# ANALOG_INPUT.net
KiCad netlist of a schematic drawn in Altium Designer
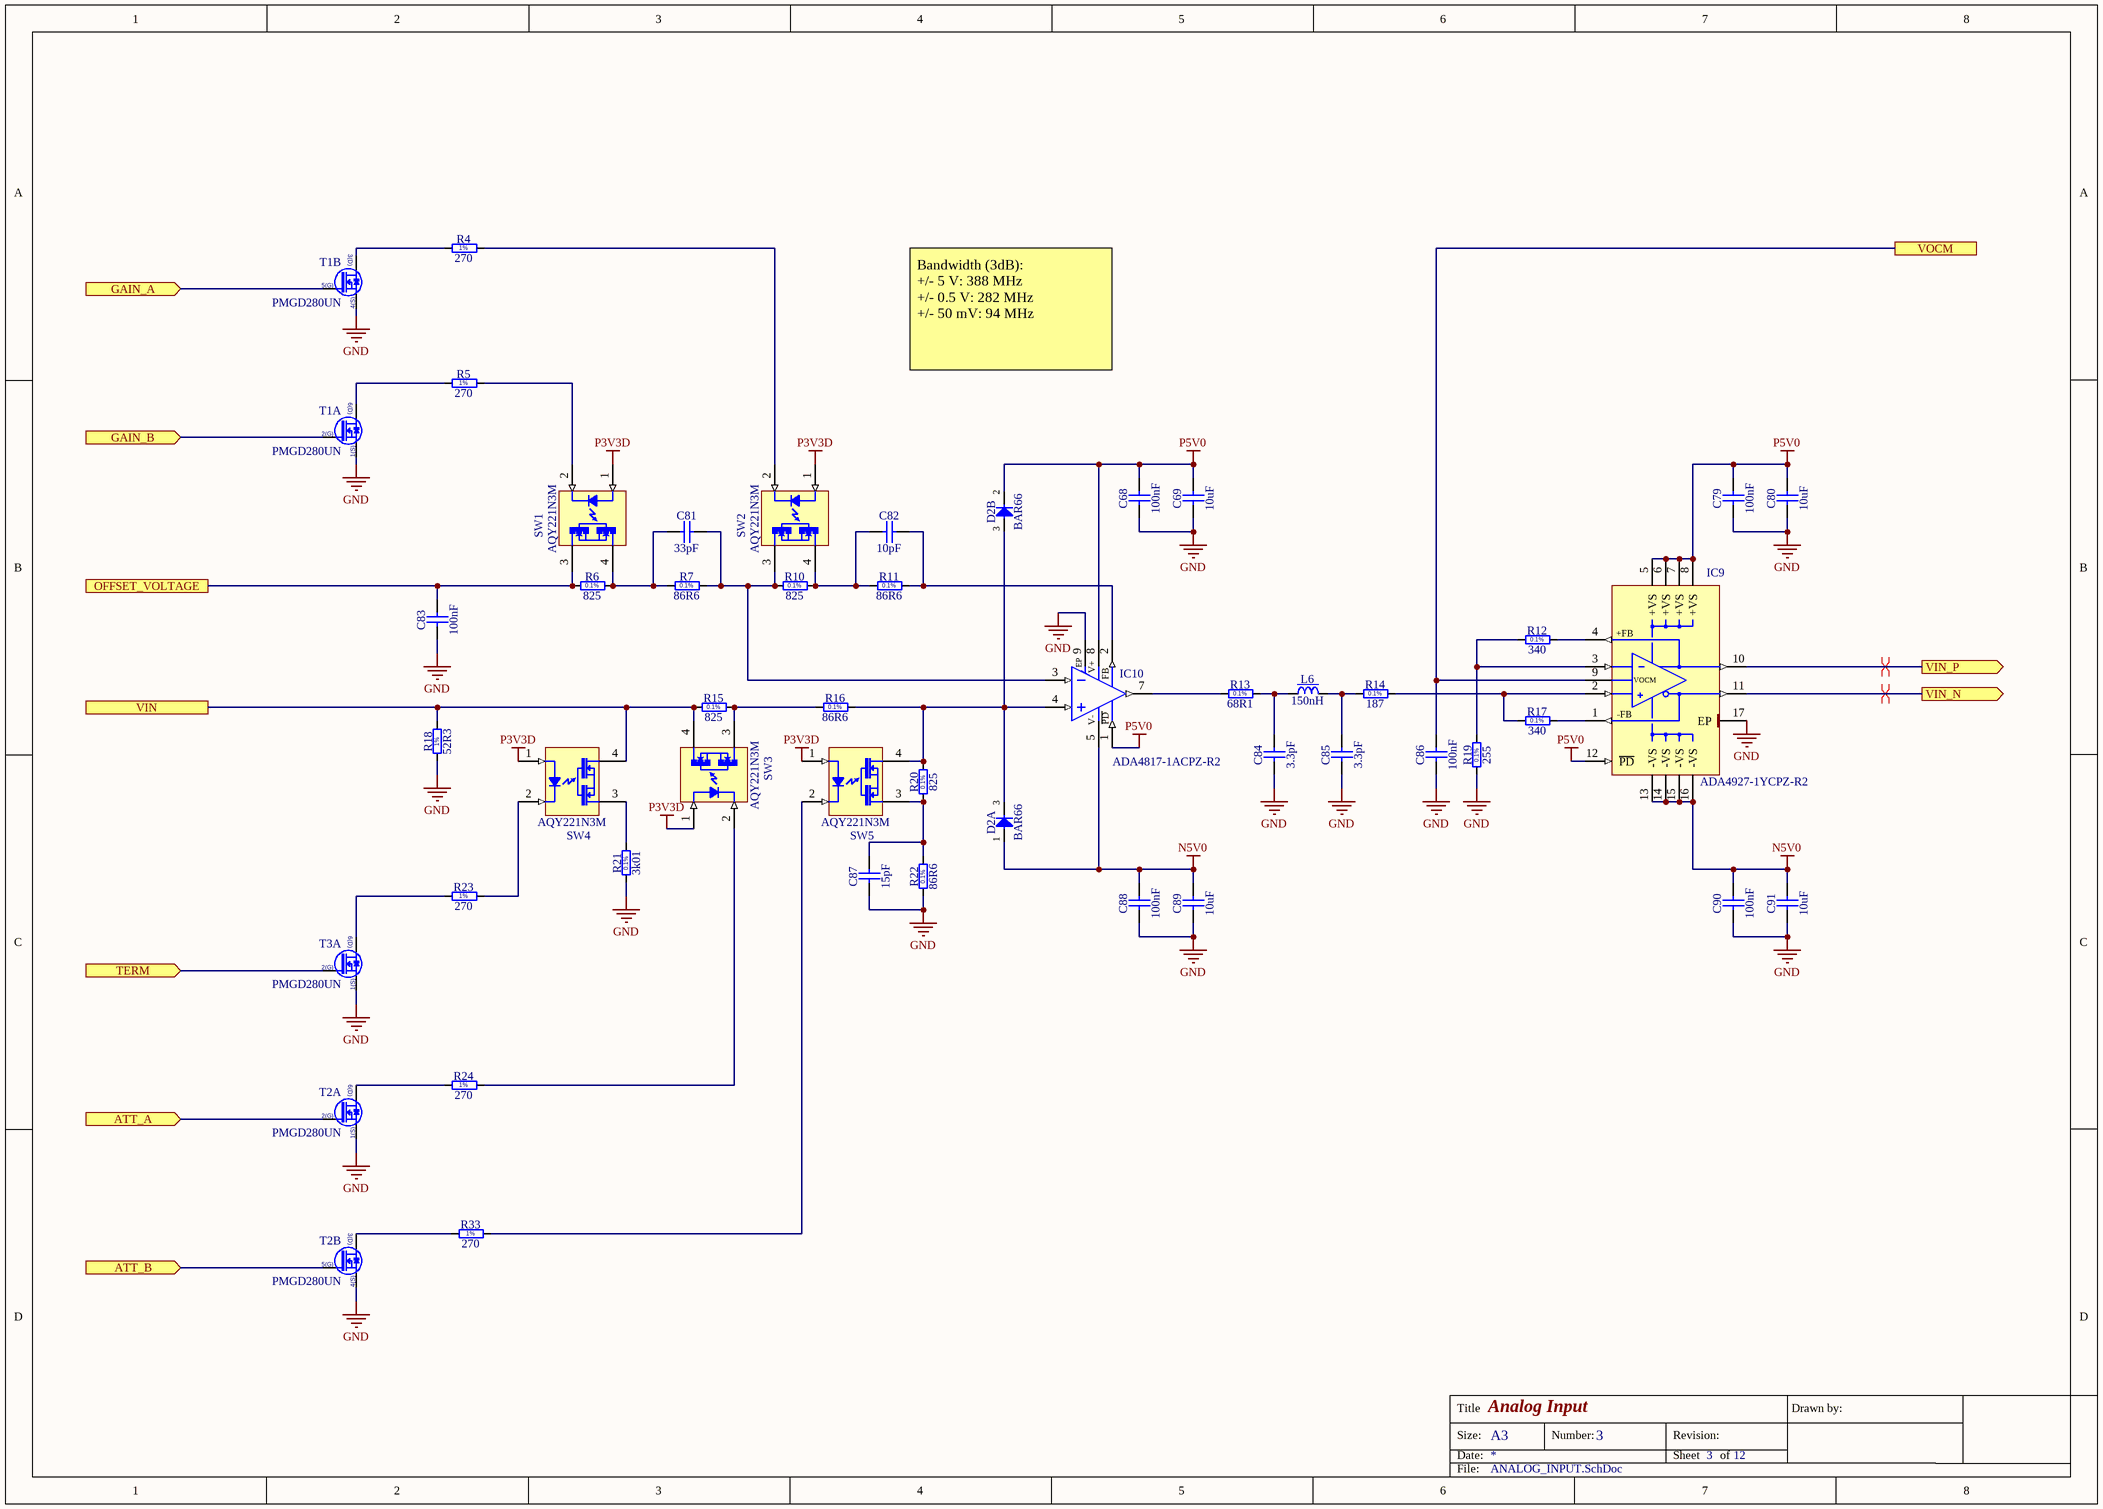
[diagram p0: ANALOG_INPUT.SchDoc]

(export (version "E")
  (design (tool "Eeschema 10.0.6"))
  (components
    (comp (ref "C68")
      (value "100nF")
      (footprint "CAPC1005X55N")
      (description "Non-polarised capacitor")
      (fields
        (field (name "PART NUMBER") "CC0402_100NF_16V_10%_X7R")
        (field (name "VOLTAGE") "16V")
        (field (name "AUTHOR") "CERN DEM JLC")
      )
      (libsource (lib "Capacitors") (part "Capacitor - non polarized"))
    )
    (comp (ref "C69")
      (value "10uF")
      (footprint "CAPC1608X80N")
      (description "Non-polarised capacitor")
      (fields
        (field (name "PART NUMBER") "CC0603_10UF_16V_20%_X5R")
        (field (name "VOLTAGE") "16V")
        (field (name "AUTHOR") "CERN DEM MR")
      )
      (libsource (lib "Capacitors") (part "Capacitor - non polarized"))
    )
    (comp (ref "C79")
      (value "100nF")
      (footprint "CAPC1005X55N")
      (description "Non-polarised capacitor")
      (fields
        (field (name "PART NUMBER") "CC0402_100NF_16V_10%_X7R")
        (field (name "VOLTAGE") "16V")
        (field (name "AUTHOR") "CERN DEM JLC")
      )
      (libsource (lib "Capacitors") (part "Capacitor - non polarized"))
    )
    (comp (ref "C80")
      (value "10uF")
      (footprint "CAPC1608X80N")
      (description "Non-polarised capacitor")
      (fields
        (field (name "PART NUMBER") "CC0603_10UF_16V_20%_X5R")
        (field (name "VOLTAGE") "16V")
        (field (name "AUTHOR") "CERN DEM MR")
      )
      (libsource (lib "Capacitors") (part "Capacitor - non polarized"))
    )
    (comp (ref "C81")
      (value "33pF")
      (footprint "CAPC1608X87N")
      (description "Non-polarised capacitor")
      (fields
        (field (name "PART NUMBER") "CC0603_33PF_50V_5%_NP0")
        (field (name "VOLTAGE") "50V")
        (field (name "AUTHOR") "CERN DEM JLC")
      )
      (libsource (lib "Capacitors") (part "Capacitor - non polarized"))
    )
    (comp (ref "C82")
      (value "10pF")
      (footprint "CAPC1608X87N")
      (description "Non-polarised capacitor")
      (fields
        (field (name "PART NUMBER") "CC0603_10PF_50V_5%_NP0")
        (field (name "VOLTAGE") "50V")
        (field (name "AUTHOR") "CERN DEM JLC")
      )
      (libsource (lib "Capacitors") (part "Capacitor - non polarized"))
    )
    (comp (ref "C83")
      (value "100nF")
      (footprint "CAPC1005X55N")
      (description "Non-polarised capacitor")
      (fields
        (field (name "PART NUMBER") "CC0402_100NF_16V_10%_X7R")
        (field (name "VOLTAGE") "16V")
        (field (name "AUTHOR") "CERN DEM JLC")
      )
      (libsource (lib "Capacitors") (part "Capacitor - non polarized"))
    )
    (comp (ref "C84")
      (value "3.3pF")
      (footprint "CAPC1005X55N")
      (description "Non-polarised capacitor")
      (fields
        (field (name "PART NUMBER") "CC0402_3.3PF_50V_0.25PF_C0G")
        (field (name "VOLTAGE") "50V")
        (field (name "AUTHOR") "CERN DEM JLC")
      )
      (libsource (lib "Capacitors") (part "Capacitor - non polarized"))
    )
    (comp (ref "C85")
      (value "3.3pF")
      (footprint "CAPC1005X55N")
      (description "Non-polarised capacitor")
      (fields
        (field (name "PART NUMBER") "CC0402_3.3PF_50V_0.25PF_C0G")
        (field (name "VOLTAGE") "50V")
        (field (name "AUTHOR") "CERN DEM JLC")
      )
      (libsource (lib "Capacitors") (part "Capacitor - non polarized"))
    )
    (comp (ref "C86")
      (value "100nF")
      (footprint "CAPC1005X55N")
      (description "Non-polarised capacitor")
      (fields
        (field (name "PART NUMBER") "CC0402_100NF_16V_10%_X7R")
        (field (name "VOLTAGE") "16V")
        (field (name "AUTHOR") "CERN DEM JLC")
      )
      (libsource (lib "Capacitors") (part "Capacitor - non polarized"))
    )
    (comp (ref "C87")
      (value "15pF")
      (footprint "CAPC1005X55N")
      (description "Non-polarised capacitor")
      (fields
        (field (name "PART NUMBER") "CC0402_15PF_50V_5%_C0G")
        (field (name "VOLTAGE") "50V")
        (field (name "AUTHOR") "CERN DEM JLC")
      )
      (libsource (lib "Capacitors") (part "Capacitor - non polarized"))
    )
    (comp (ref "C88")
      (value "100nF")
      (footprint "CAPC1005X55N")
      (description "Non-polarised capacitor")
      (fields
        (field (name "PART NUMBER") "CC0402_100NF_16V_10%_X7R")
        (field (name "VOLTAGE") "16V")
        (field (name "AUTHOR") "CERN DEM JLC")
      )
      (libsource (lib "Capacitors") (part "Capacitor - non polarized"))
    )
    (comp (ref "C89")
      (value "10uF")
      (footprint "CAPC1608X80N")
      (description "Non-polarised capacitor")
      (fields
        (field (name "PART NUMBER") "CC0603_10UF_16V_20%_X5R")
        (field (name "VOLTAGE") "16V")
        (field (name "AUTHOR") "CERN DEM MR")
      )
      (libsource (lib "Capacitors") (part "Capacitor - non polarized"))
    )
    (comp (ref "C90")
      (value "100nF")
      (footprint "CAPC1005X55N")
      (description "Non-polarised capacitor")
      (fields
        (field (name "PART NUMBER") "CC0402_100NF_16V_10%_X7R")
        (field (name "VOLTAGE") "16V")
        (field (name "AUTHOR") "CERN DEM JLC")
      )
      (libsource (lib "Capacitors") (part "Capacitor - non polarized"))
    )
    (comp (ref "C91")
      (value "10uF")
      (footprint "CAPC1608X80N")
      (description "Non-polarised capacitor")
      (fields
        (field (name "PART NUMBER") "CC0603_10UF_16V_20%_X5R")
        (field (name "VOLTAGE") "16V")
        (field (name "AUTHOR") "CERN DEM MR")
      )
      (libsource (lib "Capacitors") (part "Capacitor - non polarized"))
    )
    (comp (ref "D2")
      (value "BAR66")
      (footprint "SOT95P240X110-3N")
      (description "Serial Diode")
      (fields
        (field (name "VOLTAGE") "150V")
        (field (name "POWER") "250mA")
        (field (name "AUTHOR") "CERN DEM JLC")
      )
      (libsource (lib "ICs And Semiconductors") (part "Diode x2 A1C3_A3C2"))
    )
    (comp (ref "IC9")
      (value "ADA4927-1YCPZ-R2")
      (footprint "QFN50P300X300X100-17N-S145")
      (description "Ultralow Distortion Current Feedback Differential ADC Driver")
      (fields (field (name "MANUFACTURER") "ANALOG DEVICES") (field (name "AUTHOR") "CERN DEM JLC"))
      (libsource (lib "ICs And Semiconductors") (part "ADA4927-1"))
    )
    (comp (ref "IC10")
      (value "ADA4817-1ACPZ-R2")
      (footprint "SON50P300X300X90-9N-R160X189")
      (description "Low Noise, 1GHz FastFEET Operational Amplifier")
      (fields (field (name "MANUFACTURER") "ANALOG DEVICES") (field (name "AUTHOR") "CERN DEM JLC"))
      (libsource (lib "ICs And Semiconductors") (part "ADA4817-1ACPZ"))
    )
    (comp (ref "L6")
      (value "150nH")
      (footprint "IND_COILCRAFT_0805CS")
      (description "Inductor With Core")
      (fields
        (field (name "PART NUMBER") "IND_150NH_2%_COILCRAFT_0805CS")
        (field (name "POWER") "400mA")
        (field (name "AUTHOR") "CERN DEM JLC")
      )
      (libsource (lib "Inductors & Transformers") (part "Inductor With Magnetic core"))
    )
    (comp (ref "R4")
      (value "270")
      (footprint "RESC1608X55N")
      (description "Resistor - 1%")
      (fields
        (field (name "PART NUMBER") "R0603_270R_1%_0.1W_100PPM")
        (field (name "POWER") "0.1W")
        (field (name "AUTHOR") "CERN DEM JLC")
      )
      (libsource (lib "Resistors") (part "Resistor - 1%"))
    )
    (comp (ref "R5")
      (value "270")
      (footprint "RESC1608X55N")
      (description "Resistor - 1%")
      (fields
        (field (name "PART NUMBER") "R0603_270R_1%_0.1W_100PPM")
        (field (name "POWER") "0.1W")
        (field (name "AUTHOR") "CERN DEM JLC")
      )
      (libsource (lib "Resistors") (part "Resistor - 1%"))
    )
    (comp (ref "R6")
      (value "825")
      (footprint "RESC1608X55N")
      (description "Resistor - 0.1%")
      (fields
        (field (name "PART NUMBER") "R0603_825R_0.1%_0.063W_10PPM")
        (field (name "POWER") "0.063W")
        (field (name "AUTHOR") "CERN DEM JLC")
      )
      (libsource (lib "Resistors") (part "Resistor - 0.1%"))
    )
    (comp (ref "R7")
      (value "86R6")
      (footprint "RESC1608X55N")
      (description "Resistor - 0.1%")
      (fields
        (field (name "PART NUMBER") "R0603_86R6_0.1%_0.1W_15PPM")
        (field (name "POWER") "0.1W")
        (field (name "AUTHOR") "CERN DEM JLC")
      )
      (libsource (lib "Resistors") (part "Resistor - 0.1%"))
    )
    (comp (ref "R10")
      (value "825")
      (footprint "RESC1608X55N")
      (description "Resistor - 0.1%")
      (fields
        (field (name "PART NUMBER") "R0603_825R_0.1%_0.063W_10PPM")
        (field (name "POWER") "0.063W")
        (field (name "AUTHOR") "CERN DEM JLC")
      )
      (libsource (lib "Resistors") (part "Resistor - 0.1%"))
    )
    (comp (ref "R11")
      (value "86R6")
      (footprint "RESC1608X55N")
      (description "Resistor - 0.1%")
      (fields
        (field (name "PART NUMBER") "R0603_86R6_0.1%_0.1W_15PPM")
        (field (name "POWER") "0.1W")
        (field (name "AUTHOR") "CERN DEM JLC")
      )
      (libsource (lib "Resistors") (part "Resistor - 0.1%"))
    )
    (comp (ref "R12")
      (value "340")
      (footprint "RESC1608X55N")
      (description "Resistor - 0.1%")
      (fields
        (field (name "PART NUMBER") "R0603_340R_0.1%_0.063W_10PPM")
        (field (name "POWER") "0.063W")
        (field (name "AUTHOR") "CERN DEM JLC")
      )
      (libsource (lib "Resistors") (part "Resistor - 0.1%"))
    )
    (comp (ref "R13")
      (value "68R1")
      (footprint "RESC1608X55N")
      (description "Resistor - 0.1%")
      (fields
        (field (name "PART NUMBER") "R0603_68R1_0.1%_0.063W_10PPM")
        (field (name "POWER") "0.063W")
        (field (name "AUTHOR") "CERN DEM JLC")
      )
      (libsource (lib "Resistors") (part "Resistor - 0.1%"))
    )
    (comp (ref "R14")
      (value "187")
      (footprint "RESC1608X55N")
      (description "Resistor - 0.1%")
      (fields
        (field (name "PART NUMBER") "R0603_187R_0.1%_0.063W_10PPM")
        (field (name "POWER") "0.063W")
        (field (name "AUTHOR") "CERN DEM JLC")
      )
      (libsource (lib "Resistors") (part "Resistor - 0.1%"))
    )
    (comp (ref "R15")
      (value "825")
      (footprint "RESC1608X55N")
      (description "Resistor - 0.1%")
      (fields
        (field (name "PART NUMBER") "R0603_825R_0.1%_0.063W_10PPM")
        (field (name "POWER") "0.063W")
        (field (name "AUTHOR") "CERN DEM JLC")
      )
      (libsource (lib "Resistors") (part "Resistor - 0.1%"))
    )
    (comp (ref "R16")
      (value "86R6")
      (footprint "RESC1608X55N")
      (description "Resistor - 0.1%")
      (fields
        (field (name "PART NUMBER") "R0603_86R6_0.1%_0.1W_15PPM")
        (field (name "POWER") "0.1W")
        (field (name "AUTHOR") "CERN DEM JLC")
      )
      (libsource (lib "Resistors") (part "Resistor - 0.1%"))
    )
    (comp (ref "R17")
      (value "340")
      (footprint "RESC1608X55N")
      (description "Resistor - 0.1%")
      (fields
        (field (name "PART NUMBER") "R0603_340R_0.1%_0.063W_10PPM")
        (field (name "POWER") "0.063W")
        (field (name "AUTHOR") "CERN DEM JLC")
      )
      (libsource (lib "Resistors") (part "Resistor - 0.1%"))
    )
    (comp (ref "R18")
      (value "52R3")
      (footprint "RESC6331X70N")
      (description "Resistor - 1%")
      (fields
        (field (name "PART NUMBER") "R2512_52R3_1%_1W_100PPM")
        (field (name "POWER") "1W")
        (field (name "AUTHOR") "*")
      )
      (libsource (lib "FMC_ADC") (part "R2512_52R3_1%_1W_100PPM"))
    )
    (comp (ref "R19")
      (value "255")
      (footprint "RESC1608X55N")
      (description "Resistor - 0.1%")
      (fields
        (field (name "PART NUMBER") "R0603_255R_0.1%_0.063W_10PPM")
        (field (name "POWER") "0.063W")
        (field (name "AUTHOR") "CERN DEM JLC")
      )
      (libsource (lib "Resistors") (part "Resistor - 0.1%"))
    )
    (comp (ref "R20")
      (value "825")
      (footprint "RESC1608X55N")
      (description "Resistor - 0.1%")
      (fields
        (field (name "PART NUMBER") "R0603_825R_0.1%_0.063W_10PPM")
        (field (name "POWER") "0.063W")
        (field (name "AUTHOR") "CERN DEM JLC")
      )
      (libsource (lib "Resistors") (part "Resistor - 0.1%"))
    )
    (comp (ref "R21")
      (value "3k01")
      (footprint "RESC1608X55N")
      (description "Resistor - 0.1%")
      (fields
        (field (name "PART NUMBER") "R0603_3K01_0.1%_0.063W_10PPM")
        (field (name "POWER") "0.063W")
        (field (name "AUTHOR") "CERN DEM JLC")
      )
      (libsource (lib "Resistors") (part "Resistor - 0.1%"))
    )
    (comp (ref "R22")
      (value "86R6")
      (footprint "RESC1608X55N")
      (description "Resistor - 0.1%")
      (fields
        (field (name "PART NUMBER") "R0603_86R6_0.1%_0.1W_15PPM")
        (field (name "POWER") "0.1W")
        (field (name "AUTHOR") "CERN DEM JLC")
      )
      (libsource (lib "Resistors") (part "Resistor - 0.1%"))
    )
    (comp (ref "R23")
      (value "270")
      (footprint "RESC1608X55N")
      (description "Resistor - 1%")
      (fields
        (field (name "PART NUMBER") "R0603_270R_1%_0.1W_100PPM")
        (field (name "POWER") "0.1W")
        (field (name "AUTHOR") "CERN DEM JLC")
      )
      (libsource (lib "Resistors") (part "Resistor - 1%"))
    )
    (comp (ref "R24")
      (value "270")
      (footprint "RESC1608X55N")
      (description "Resistor - 1%")
      (fields
        (field (name "PART NUMBER") "R0603_270R_1%_0.1W_100PPM")
        (field (name "POWER") "0.1W")
        (field (name "AUTHOR") "CERN DEM JLC")
      )
      (libsource (lib "Resistors") (part "Resistor - 1%"))
    )
    (comp (ref "R33")
      (value "270")
      (footprint "RESC1608X55N")
      (description "Resistor - 1%")
      (fields
        (field (name "PART NUMBER") "R0603_270R_1%_0.1W_100PPM")
        (field (name "POWER") "0.1W")
        (field (name "AUTHOR") "CERN DEM JLC")
      )
      (libsource (lib "Resistors") (part "Resistor - 1%"))
    )
    (comp (ref "SW1")
      (value "AQY221N3M")
      (footprint "PANASONIC_AQY22(SON)")
      (description "PhotoMOS Relay")
      (fields (field (name "MANUFACTURER") "PANASONIC ELECTRIC WORKS") (field (name "AUTHOR") "CERN DEM JLC"))
      (libsource (lib "ICs And Semiconductors") (part "PhotoMOS Relay x1 Type2"))
    )
    (comp (ref "SW2")
      (value "AQY221N3M")
      (footprint "PANASONIC_AQY22(SON)")
      (description "PhotoMOS Relay")
      (fields (field (name "MANUFACTURER") "PANASONIC ELECTRIC WORKS") (field (name "AUTHOR") "CERN DEM JLC"))
      (libsource (lib "ICs And Semiconductors") (part "PhotoMOS Relay x1 Type2"))
    )
    (comp (ref "SW3")
      (value "AQY221N3M")
      (footprint "PANASONIC_AQY22(SON)")
      (description "PhotoMOS Relay")
      (fields (field (name "MANUFACTURER") "PANASONIC ELECTRIC WORKS") (field (name "AUTHOR") "CERN DEM JLC"))
      (libsource (lib "") (part "PhotoMOS Relay x1 Type2_2"))
    )
    (comp (ref "SW4")
      (value "AQY221N3M")
      (footprint "PANASONIC_AQY22(SON)")
      (description "PhotoMOS Relay")
      (fields (field (name "MANUFACTURER") "PANASONIC ELECTRIC WORKS") (field (name "AUTHOR") "CERN DEM JLC"))
      (libsource (lib "") (part "PhotoMOS Relay x1 Type2_1"))
    )
    (comp (ref "SW5")
      (value "AQY221N3M")
      (footprint "PANASONIC_AQY22(SON)")
      (description "PhotoMOS Relay")
      (fields (field (name "MANUFACTURER") "PANASONIC ELECTRIC WORKS") (field (name "AUTHOR") "CERN DEM JLC"))
      (libsource (lib "") (part "PhotoMOS Relay x1 Type2_1"))
    )
    (comp (ref "T1")
      (value "PMGD280UN")
      (footprint "SOT65P210X110-6N")
      (description "Dual N-Channel micro TrenchMOS™ Ultra Low Level FET")
      (fields (field (name "MANUFACTURER") "NXP SEMICONDUCTORS") (field (name "AUTHOR") "CERN DEM JLC"))
      (libsource (lib "ICs And Semiconductors") (part "PMGD280UN"))
    )
    (comp (ref "T2")
      (value "PMGD280UN")
      (footprint "SOT65P210X110-6N")
      (description "Dual N-Channel micro TrenchMOS™ Ultra Low Level FET")
      (fields (field (name "MANUFACTURER") "NXP SEMICONDUCTORS") (field (name "AUTHOR") "CERN DEM JLC"))
      (libsource (lib "ICs And Semiconductors") (part "PMGD280UN"))
    )
    (comp (ref "T3")
      (value "PMGD280UN")
      (footprint "SOT65P210X110-6N")
      (description "Dual N-Channel micro TrenchMOS™ Ultra Low Level FET")
      (fields (field (name "MANUFACTURER") "NXP SEMICONDUCTORS") (field (name "AUTHOR") "CERN DEM JLC"))
      (libsource (lib "ICs And Semiconductors") (part "PMGD280UN"))
    )
  )
  (nets
    (net (code "1") (name "/ATT_A") (class "Default")
      (node (ref "T2") (pin "2") (pinfunction "G_2") (pintype "passive"))
    )
    (net (code "2") (name "/ATT_B") (class "Default")
      (node (ref "T2") (pin "5") (pinfunction "G_5") (pintype "passive"))
    )
    (net (code "3") (name "/GAIN_A") (class "Default")
      (node (ref "T1") (pin "5") (pinfunction "G_5") (pintype "passive"))
    )
    (net (code "4") (name "/GAIN_B") (class "Default")
      (node (ref "T1") (pin "2") (pinfunction "G_2") (pintype "passive"))
    )
    (net (code "5") (name "/OFFSET_VOLTAGE") (class "Default")
      (node (ref "C83") (pin "2") (pinfunction "2_2") (pintype "passive"))
      (node (ref "R6") (pin "1") (pinfunction "1_1") (pintype "passive"))
      (node (ref "SW1") (pin "3") (pinfunction "C_3") (pintype "open_collector"))
    )
    (net (code "6") (name "/TERM") (class "Default")
      (node (ref "T3") (pin "2") (pinfunction "G_2") (pintype "passive"))
    )
    (net (code "7") (name "/VIN") (class "Default")
      (node (ref "R15") (pin "1") (pinfunction "1_1") (pintype "passive"))
      (node (ref "R18") (pin "2") (pinfunction "2_2") (pintype "passive"))
      (node (ref "SW3") (pin "4") (pinfunction "E_4") (pintype "open_emitter"))
      (node (ref "SW4") (pin "4") (pinfunction "E_4") (pintype "open_emitter"))
    )
    (net (code "8") (name "/VIN_N") (class "Default")
      (node (ref "IC9") (pin "11") (pinfunction "-OUT_11") (pintype "output"))
    )
    (net (code "9") (name "/VIN_P") (class "Default")
      (node (ref "IC9") (pin "10") (pinfunction "+OUT_10") (pintype "output"))
    )
    (net (code "10") (name "/VOCM") (class "Default")
      (node (ref "C86") (pin "2") (pinfunction "2_2") (pintype "passive"))
      (node (ref "IC9") (pin "9") (pinfunction "VOCM_9") (pintype "passive"))
    )
    (net (code "11") (name "GND") (class "Default")
      (node (ref "C68") (pin "1") (pinfunction "1_1") (pintype "passive"))
      (node (ref "C69") (pin "1") (pinfunction "1_1") (pintype "passive"))
      (node (ref "C79") (pin "1") (pinfunction "1_1") (pintype "passive"))
      (node (ref "C80") (pin "1") (pinfunction "1_1") (pintype "passive"))
      (node (ref "C83") (pin "1") (pinfunction "1_1") (pintype "passive"))
      (node (ref "C84") (pin "1") (pinfunction "1_1") (pintype "passive"))
      (node (ref "C85") (pin "1") (pinfunction "1_1") (pintype "passive"))
      (node (ref "C86") (pin "1") (pinfunction "1_1") (pintype "passive"))
      (node (ref "C87") (pin "1") (pinfunction "1_1") (pintype "passive"))
      (node (ref "C88") (pin "1") (pinfunction "1_1") (pintype "passive"))
      (node (ref "C89") (pin "1") (pinfunction "1_1") (pintype "passive"))
      (node (ref "C90") (pin "1") (pinfunction "1_1") (pintype "passive"))
      (node (ref "C91") (pin "1") (pinfunction "1_1") (pintype "passive"))
      (node (ref "IC10") (pin "9") (pinfunction "EP_9") (pintype "power_in"))
      (node (ref "IC9") (pin "17") (pinfunction "EP_17") (pintype "power_in"))
      (node (ref "R18") (pin "1") (pinfunction "1_1") (pintype "passive"))
      (node (ref "R19") (pin "1") (pinfunction "1_1") (pintype "passive"))
      (node (ref "R21") (pin "1") (pinfunction "1_1") (pintype "passive"))
      (node (ref "R22") (pin "1") (pinfunction "1_1") (pintype "passive"))
      (node (ref "T1") (pin "1") (pinfunction "S_1") (pintype "passive"))
      (node (ref "T1") (pin "4") (pinfunction "S_4") (pintype "passive"))
      (node (ref "T2") (pin "1") (pinfunction "S_1") (pintype "passive"))
      (node (ref "T2") (pin "4") (pinfunction "S_4") (pintype "passive"))
      (node (ref "T3") (pin "1") (pinfunction "S_1") (pintype "passive"))
    )
    (net (code "12") (name "N5V0") (class "Default")
      (node (ref "C88") (pin "2") (pinfunction "2_2") (pintype "passive"))
      (node (ref "C89") (pin "2") (pinfunction "2_2") (pintype "passive"))
      (node (ref "C90") (pin "2") (pinfunction "2_2") (pintype "passive"))
      (node (ref "C91") (pin "2") (pinfunction "2_2") (pintype "passive"))
      (node (ref "D2") (pin "1") (pinfunction "A_1") (pintype "passive"))
      (node (ref "IC10") (pin "5") (pinfunction "-Vs_5") (pintype "power_in"))
      (node (ref "IC9") (pin "13") (pinfunction "-VS_13") (pintype "power_in"))
      (node (ref "IC9") (pin "14") (pinfunction "-VS_14") (pintype "power_in"))
      (node (ref "IC9") (pin "15") (pinfunction "-VS_15") (pintype "power_in"))
      (node (ref "IC9") (pin "16") (pinfunction "-VS_16") (pintype "power_in"))
    )
    (net (code "13") (name "Net-(C84-Pad2)") (class "Default")
      (node (ref "C84") (pin "2") (pinfunction "2_2") (pintype "passive"))
      (node (ref "L6") (pin "1") (pinfunction "1_1") (pintype "passive"))
      (node (ref "R13") (pin "2") (pinfunction "2_2") (pintype "passive"))
    )
    (net (code "14") (name "Net-(C85-Pad2)") (class "Default")
      (node (ref "C85") (pin "2") (pinfunction "2_2") (pintype "passive"))
      (node (ref "L6") (pin "2") (pinfunction "2_2") (pintype "passive"))
      (node (ref "R14") (pin "1") (pinfunction "1_1") (pintype "passive"))
    )
    (net (code "15") (name "Net-(D2A-COMAC)") (class "Default")
      (node (ref "D2") (pin "3") (pinfunction "COMAC_3") (pintype "passive"))
      (node (ref "IC10") (pin "4") (pinfunction "IN+_4") (pintype "input"))
      (node (ref "R16") (pin "2") (pinfunction "2_2") (pintype "passive"))
      (node (ref "R20") (pin "2") (pinfunction "2_2") (pintype "passive"))
      (node (ref "SW5") (pin "4") (pinfunction "E_4") (pintype "open_emitter"))
    )
    (net (code "16") (name "Net-(IC9-+FB)") (class "Default")
      (node (ref "IC9") (pin "4") (pinfunction "+FB_4") (pintype "output"))
      (node (ref "R12") (pin "2") (pinfunction "2_2") (pintype "passive"))
    )
    (net (code "17") (name "Net-(IC9-+IN)") (class "Default")
      (node (ref "IC9") (pin "2") (pinfunction "+IN_2") (pintype "input"))
      (node (ref "R14") (pin "2") (pinfunction "2_2") (pintype "passive"))
      (node (ref "R17") (pin "1") (pinfunction "1_1") (pintype "passive"))
    )
    (net (code "18") (name "Net-(IC9--FB)") (class "Default")
      (node (ref "IC9") (pin "1") (pinfunction "-FB_1") (pintype "output"))
      (node (ref "R17") (pin "2") (pinfunction "2_2") (pintype "passive"))
    )
    (net (code "19") (name "Net-(IC9--IN)") (class "Default")
      (node (ref "IC9") (pin "3") (pinfunction "-IN_3") (pintype "input"))
      (node (ref "R12") (pin "1") (pinfunction "1_1") (pintype "passive"))
      (node (ref "R19") (pin "2") (pinfunction "2_2") (pintype "passive"))
    )
    (net (code "20") (name "Net-(IC10-FB)") (class "Default")
      (node (ref "C82") (pin "2") (pinfunction "2_2") (pintype "passive"))
      (node (ref "IC10") (pin "2") (pinfunction "FB_2") (pintype "output"))
      (node (ref "R11") (pin "2") (pinfunction "2_2") (pintype "passive"))
    )
    (net (code "21") (name "Net-(IC10-IN-)") (class "Default")
      (node (ref "C81") (pin "2") (pinfunction "2_2") (pintype "passive"))
      (node (ref "IC10") (pin "3") (pinfunction "IN-_3") (pintype "input"))
      (node (ref "R10") (pin "1") (pinfunction "1_1") (pintype "passive"))
      (node (ref "R7") (pin "2") (pinfunction "2_2") (pintype "passive"))
      (node (ref "SW2") (pin "3") (pinfunction "C_3") (pintype "open_collector"))
    )
    (net (code "22") (name "Net-(IC10-OUT)") (class "Default")
      (node (ref "IC10") (pin "7") (pinfunction "OUT_7") (pintype "output"))
      (node (ref "R13") (pin "1") (pinfunction "1_1") (pintype "passive"))
    )
    (net (code "23") (name "Net-(SW1-E)") (class "Default")
      (node (ref "C81") (pin "1") (pinfunction "1_1") (pintype "passive"))
      (node (ref "R6") (pin "2") (pinfunction "2_2") (pintype "passive"))
      (node (ref "R7") (pin "1") (pinfunction "1_1") (pintype "passive"))
      (node (ref "SW1") (pin "4") (pinfunction "E_4") (pintype "open_emitter"))
    )
    (net (code "24") (name "Net-(SW1-K)") (class "Default")
      (node (ref "R5") (pin "2") (pinfunction "2_2") (pintype "passive"))
      (node (ref "SW1") (pin "2") (pinfunction "K_2") (pintype "input"))
    )
    (net (code "25") (name "Net-(SW2-E)") (class "Default")
      (node (ref "C82") (pin "1") (pinfunction "1_1") (pintype "passive"))
      (node (ref "R10") (pin "2") (pinfunction "2_2") (pintype "passive"))
      (node (ref "R11") (pin "1") (pinfunction "1_1") (pintype "passive"))
      (node (ref "SW2") (pin "4") (pinfunction "E_4") (pintype "open_emitter"))
    )
    (net (code "26") (name "Net-(SW2-K)") (class "Default")
      (node (ref "R4") (pin "2") (pinfunction "2_2") (pintype "passive"))
      (node (ref "SW2") (pin "2") (pinfunction "K_2") (pintype "input"))
    )
    (net (code "27") (name "Net-(SW3-C)") (class "Default")
      (node (ref "R15") (pin "2") (pinfunction "2_2") (pintype "passive"))
      (node (ref "R16") (pin "1") (pinfunction "1_1") (pintype "passive"))
      (node (ref "SW3") (pin "3") (pinfunction "C_3") (pintype "open_collector"))
    )
    (net (code "28") (name "Net-(SW3-K)") (class "Default")
      (node (ref "R24") (pin "2") (pinfunction "2_2") (pintype "passive"))
      (node (ref "SW3") (pin "2") (pinfunction "K_2") (pintype "input"))
    )
    (net (code "29") (name "Net-(SW4-C)") (class "Default")
      (node (ref "R21") (pin "2") (pinfunction "2_2") (pintype "passive"))
      (node (ref "SW4") (pin "3") (pinfunction "C_3") (pintype "open_collector"))
    )
    (net (code "30") (name "Net-(SW4-K)") (class "Default")
      (node (ref "R23") (pin "2") (pinfunction "2_2") (pintype "passive"))
      (node (ref "SW4") (pin "2") (pinfunction "K_2") (pintype "input"))
    )
    (net (code "31") (name "Net-(SW5-C)") (class "Default")
      (node (ref "C87") (pin "2") (pinfunction "2_2") (pintype "passive"))
      (node (ref "R20") (pin "1") (pinfunction "1_1") (pintype "passive"))
      (node (ref "R22") (pin "2") (pinfunction "2_2") (pintype "passive"))
      (node (ref "SW5") (pin "3") (pinfunction "C_3") (pintype "open_collector"))
    )
    (net (code "32") (name "Net-(SW5-K)") (class "Default")
      (node (ref "R33") (pin "2") (pinfunction "2_2") (pintype "passive"))
      (node (ref "SW5") (pin "2") (pinfunction "K_2") (pintype "input"))
    )
    (net (code "33") (name "Net-(T1A-D)") (class "Default")
      (node (ref "R5") (pin "1") (pinfunction "1_1") (pintype "passive"))
      (node (ref "T1") (pin "6") (pinfunction "D_6") (pintype "passive"))
    )
    (net (code "34") (name "Net-(T1B-D)") (class "Default")
      (node (ref "R4") (pin "1") (pinfunction "1_1") (pintype "passive"))
      (node (ref "T1") (pin "3") (pinfunction "D_3") (pintype "passive"))
    )
    (net (code "35") (name "Net-(T2A-D)") (class "Default")
      (node (ref "R24") (pin "1") (pinfunction "1_1") (pintype "passive"))
      (node (ref "T2") (pin "6") (pinfunction "D_6") (pintype "passive"))
    )
    (net (code "36") (name "Net-(T2B-D)") (class "Default")
      (node (ref "R33") (pin "1") (pinfunction "1_1") (pintype "passive"))
      (node (ref "T2") (pin "3") (pinfunction "D_3") (pintype "passive"))
    )
    (net (code "37") (name "Net-(T3A-D)") (class "Default")
      (node (ref "R23") (pin "1") (pinfunction "1_1") (pintype "passive"))
      (node (ref "T3") (pin "6") (pinfunction "D_6") (pintype "passive"))
    )
    (net (code "38") (name "P3V3D") (class "Default")
      (node (ref "SW1") (pin "1") (pinfunction "A_1") (pintype "input"))
      (node (ref "SW2") (pin "1") (pinfunction "A_1") (pintype "input"))
      (node (ref "SW3") (pin "1") (pinfunction "A_1") (pintype "input"))
      (node (ref "SW4") (pin "1") (pinfunction "A_1") (pintype "input"))
      (node (ref "SW5") (pin "1") (pinfunction "A_1") (pintype "input"))
    )
    (net (code "39") (name "P5V0") (class "Default")
      (node (ref "C68") (pin "2") (pinfunction "2_2") (pintype "passive"))
      (node (ref "C69") (pin "2") (pinfunction "2_2") (pintype "passive"))
      (node (ref "C79") (pin "2") (pinfunction "2_2") (pintype "passive"))
      (node (ref "C80") (pin "2") (pinfunction "2_2") (pintype "passive"))
      (node (ref "D2") (pin "2") (pinfunction "C_2") (pintype "passive"))
      (node (ref "IC10") (pin "1") (pinfunction "~{PD}_1") (pintype "input"))
      (node (ref "IC10") (pin "8") (pinfunction "+Vs_8") (pintype "power_in"))
      (node (ref "IC9") (pin "12") (pinfunction "~{PD}_12") (pintype "input"))
      (node (ref "IC9") (pin "5") (pinfunction "+VS_5") (pintype "power_in"))
      (node (ref "IC9") (pin "6") (pinfunction "+VS_6") (pintype "power_in"))
      (node (ref "IC9") (pin "7") (pinfunction "+VS_7") (pintype "power_in"))
      (node (ref "IC9") (pin "8") (pinfunction "+VS_8") (pintype "power_in"))
    )
  )
)
